# Sheet2.net
KiCad netlist of a schematic drawn in Altium Designer
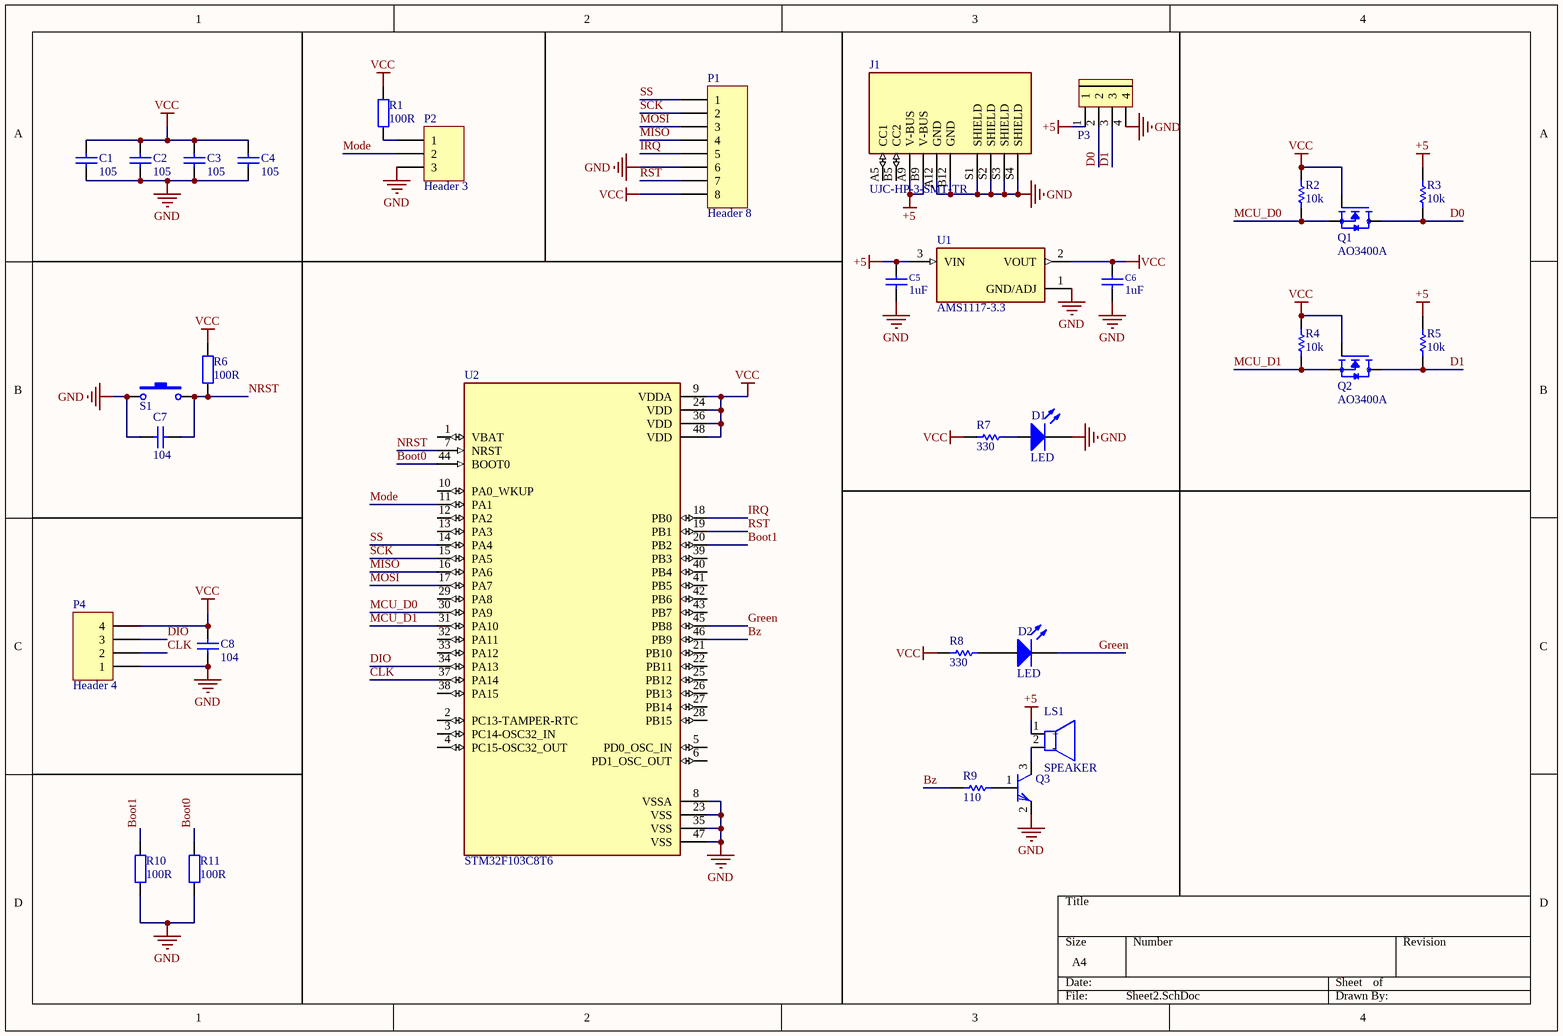
[diagram p0: Sheet2.SchDoc]

(export (version "E")
  (design (tool "Eeschema 10.0.6"))
  (components
    (comp (ref "C1")
      (value "105")
      (footprint "C-NP-0805")
      (description "Non-polarized Capacitor")
      (fields (field (name "Comment") "Cap Non-pol") (field (name "PUBLISHER") "Altium Limited"))
      (libsource (lib "Kiet") (part "Cap Non-pol"))
    )
    (comp (ref "C2")
      (value "105")
      (footprint "C-NP-0805")
      (description "Non-polarized Capacitor")
      (fields (field (name "Comment") "Cap Non-pol") (field (name "PUBLISHER") "Altium Limited"))
      (libsource (lib "Kiet") (part "Cap Non-pol"))
    )
    (comp (ref "C3")
      (value "105")
      (footprint "C-NP-0805")
      (description "Non-polarized Capacitor")
      (fields (field (name "Comment") "Cap Non-pol") (field (name "PUBLISHER") "Altium Limited"))
      (libsource (lib "Kiet") (part "Cap Non-pol"))
    )
    (comp (ref "C4")
      (value "105")
      (footprint "C-NP-0805")
      (description "Non-polarized Capacitor")
      (fields (field (name "Comment") "Cap Non-pol") (field (name "PUBLISHER") "Altium Limited"))
      (libsource (lib "Kiet") (part "Cap Non-pol"))
    )
    (comp (ref "C5")
      (value "1uF")
      (footprint "C2012-0805")
      (description "Capacitor")
      (fields (field (name "PUBLISHER") "Hoang Nguyen"))
      (libsource (lib "Kiet") (part "Capacitor"))
    )
    (comp (ref "C6")
      (value "1uF")
      (footprint "C2012-0805")
      (description "Capacitor")
      (fields (field (name "PUBLISHER") "Hoang Nguyen"))
      (libsource (lib "Kiet") (part "Capacitor"))
    )
    (comp (ref "C7")
      (value "104")
      (footprint "C-NP-0805")
      (description "Non-polarized Capacitor")
      (fields (field (name "Comment") "Cap Non-pol") (field (name "PUBLISHER") "Altium Limited"))
      (libsource (lib "Kiet") (part "Cap Non-pol"))
    )
    (comp (ref "C8")
      (value "104")
      (footprint "C-NP-0805")
      (description "Non-polarized Capacitor")
      (fields (field (name "Comment") "Cap Non-pol") (field (name "PUBLISHER") "Altium Limited"))
      (libsource (lib "Kiet") (part "Cap Non-pol"))
    )
    (comp (ref "D1")
      (value "LED")
      (footprint "LED-0805 RED")
      (description "Typical LED")
      (fields (field (name "PUBLISHER") "Altium Limited"))
      (libsource (lib "Kiet") (part "LED"))
    )
    (comp (ref "D2")
      (value "LED")
      (footprint "LED-0 3mm RED")
      (description "Typical LED")
      (fields (field (name "PUBLISHER") "Altium Limited"))
      (libsource (lib "Kiet") (part "LED"))
    )
    (comp (ref "J1")
      (value "UJC-HP-3-SMT-TR")
      (footprint "CUI_UJC-HP-3-SMT-TR")
      (libsource (lib "UJC-HP-3-SMT-TR") (part "UJC-HP-3-SMT-TR"))
    )
    (comp (ref "LS1")
      (value "SPEAKER")
      (footprint "speaker")
      (fields (field (name "PUBLISHER") "Hoang Nguyen"))
      (libsource (lib "Kiet") (part "SPEAKER"))
    )
    (comp (ref "P1")
      (value "Header 8")
      (footprint "Header 8")
      (description "Header, 8-Pin")
      (fields (field (name "PUBLISHER") "Altium Limited"))
      (libsource (lib "Kiet") (part "Header 8"))
    )
    (comp (ref "P2")
      (value "Header 3")
      (footprint "Header 3")
      (description "Header, 3-Pin")
      (fields (field (name "PUBLISHER") "Altium Limited"))
      (libsource (lib "Kiet") (part "Header 3"))
    )
    (comp (ref "P3")
      (value "BIG Header 4")
      (footprint "BIG_Header 4")
      (libsource (lib "Kiet") (part "BIG_Header 4"))
    )
    (comp (ref "P4")
      (value "Header 4")
      (footprint "Header 4")
      (description "Header, 4-Pin")
      (fields (field (name "PUBLISHER") "Altium Limited"))
      (libsource (lib "Kiet") (part "Header 4"))
    )
    (comp (ref "Q1")
      (value "AO3400A")
      (footprint "SOT95P280X125-3N")
      (description "Trans MOSFET N-CH 30V 5.7A 3-Pin SOT-23")
      (libsource (lib "AO3400A") (part "AO3400A"))
    )
    (comp (ref "Q2")
      (value "AO3400A")
      (footprint "SOT95P280X125-3N")
      (description "Trans MOSFET N-CH 30V 5.7A 3-Pin SOT-23")
      (libsource (lib "AO3400A") (part "AO3400A"))
    )
    (comp (ref "Q3")
      (value "C1815")
      (footprint "SOT23 [C1815]")
      (description "Q2SC1815")
      (fields (field (name "PUBLISHER") "Hoang Nguyen"))
      (libsource (lib "Kiet") (part "C1815"))
    )
    (comp (ref "R1")
      (value "100R")
      (footprint "DIEN TRO 0805")
      (description "RES_0805")
      (fields (field (name "Comment") "RES_SMD_0805") (field (name "PUBLISHER") "Altium Limited"))
      (libsource (lib "Kiet") (part "RES_SMD_0805"))
    )
    (comp (ref "R2")
      (value "10k")
      (footprint "R-0805")
      (description "Resistor")
      (fields (field (name "Comment") "RESISTOR") (field (name "PUBLISHER") "Altium Limited"))
      (libsource (lib "Kiet") (part "RESISTOR"))
    )
    (comp (ref "R3")
      (value "10k")
      (footprint "R-0805")
      (description "Resistor")
      (fields (field (name "Comment") "RESISTOR") (field (name "PUBLISHER") "Altium Limited"))
      (libsource (lib "Kiet") (part "RESISTOR"))
    )
    (comp (ref "R4")
      (value "10k")
      (footprint "R-0805")
      (description "Resistor")
      (fields (field (name "Comment") "RESISTOR") (field (name "PUBLISHER") "Altium Limited"))
      (libsource (lib "Kiet") (part "RESISTOR"))
    )
    (comp (ref "R5")
      (value "10k")
      (footprint "R-0805")
      (description "Resistor")
      (fields (field (name "Comment") "RESISTOR") (field (name "PUBLISHER") "Altium Limited"))
      (libsource (lib "Kiet") (part "RESISTOR"))
    )
    (comp (ref "R6")
      (value "100R")
      (footprint "DIEN TRO 0805")
      (description "RES_0805")
      (fields (field (name "Comment") "RES_SMD_0805") (field (name "PUBLISHER") "Altium Limited"))
      (libsource (lib "Kiet") (part "RES_SMD_0805"))
    )
    (comp (ref "R7")
      (value "330")
      (footprint "R-0805")
      (description "Resistor")
      (fields (field (name "Comment") "RESISTOR") (field (name "PUBLISHER") "Altium Limited"))
      (libsource (lib "Kiet") (part "RESISTOR"))
    )
    (comp (ref "R8")
      (value "330")
      (footprint "R-0805")
      (description "Resistor")
      (fields (field (name "Comment") "RESISTOR") (field (name "PUBLISHER") "Altium Limited"))
      (libsource (lib "Kiet") (part "RESISTOR"))
    )
    (comp (ref "R9")
      (value "110")
      (footprint "R-0805")
      (description "Resistor")
      (fields (field (name "Comment") "RESISTOR") (field (name "PUBLISHER") "Altium Limited"))
      (libsource (lib "Kiet") (part "RESISTOR"))
    )
    (comp (ref "R10")
      (value "100R")
      (footprint "DIEN TRO 0805")
      (description "RES_0805")
      (fields (field (name "Comment") "RES_SMD_0805") (field (name "PUBLISHER") "Altium Limited"))
      (libsource (lib "") (part "RES_SMD_0805_1"))
    )
    (comp (ref "R11")
      (value "100R")
      (footprint "DIEN TRO 0805")
      (description "RES_0805")
      (fields (field (name "Comment") "RES_SMD_0805") (field (name "PUBLISHER") "Altium Limited"))
      (libsource (lib "Kiet") (part "RES_SMD_0805"))
    )
    (comp (ref "S1")
      (value "SW-SMD")
      (footprint "SW-SMD")
      (description "Switch")
      (fields (field (name "PUBLISHER") "Altium Limited"))
      (libsource (lib "Kiet") (part "SW-SMD"))
    )
    (comp (ref "U1")
      (value "AMS1117-3.3")
      (footprint "SOT229P700X180-4N")
      (description "Sot223/Pkg 1-Amp 3.3-Volt Low Drop Out Voltage Regulatator")
      (fields (field (name "MF") "Advanced Monolithic Systems"))
      (libsource (lib "AMS1117-3.3") (part "AMS1117-3.3"))
    )
    (comp (ref "U2")
      (value "STM32F103C8T6")
      (footprint "QFP50P900X900X160-48N")
      (description "ARM® Cortex®-M3 STM32F1 Microcontroller IC 32-Bit 72MHz 64KB (64K x 8) FLASH 48-LQFP (7x7)")
      (fields (field (name "MF") "STMicroelectronics"))
      (libsource (lib "STM32F103C8T6") (part "STM32F103C8T6"))
    )
  )
  (nets
    (net (code "1") (name "+5") (class "Default")
      (node (ref "C5") (pin "2") (pinfunction "2_2") (pintype "passive"))
      (node (ref "J1") (pin "A9") (pinfunction "V-BUS_A9") (pintype "power_in"))
      (node (ref "J1") (pin "B9") (pinfunction "V-BUS_B9") (pintype "power_in"))
      (node (ref "LS1") (pin "1") (pinfunction "+_1") (pintype "passive"))
      (node (ref "P3") (pin "1") (pinfunction "1_1") (pintype "passive"))
      (node (ref "R3") (pin "2") (pinfunction "2_2") (pintype "passive"))
      (node (ref "R5") (pin "2") (pinfunction "2_2") (pintype "passive"))
      (node (ref "U1") (pin "3") (pinfunction "VIN_3") (pintype "input"))
    )
    (net (code "2") (name "/Boot0") (class "Default")
      (node (ref "R11") (pin "2") (pinfunction "2_2") (pintype "passive"))
      (node (ref "U2") (pin "44") (pinfunction "BOOT0_44") (pintype "input"))
    )
    (net (code "3") (name "/Boot1") (class "Default")
      (node (ref "R10") (pin "1") (pinfunction "1_1") (pintype "passive"))
      (node (ref "U2") (pin "20") (pinfunction "PB2_20") (pintype "bidirectional"))
    )
    (net (code "4") (name "/Bz") (class "Default")
      (node (ref "R9") (pin "1") (pinfunction "1_1") (pintype "passive"))
      (node (ref "U2") (pin "46") (pinfunction "PB9_46") (pintype "bidirectional"))
    )
    (net (code "5") (name "/CLK") (class "Default")
      (node (ref "P4") (pin "2") (pinfunction "2_2") (pintype "passive"))
      (node (ref "U2") (pin "37") (pinfunction "PA14_37") (pintype "bidirectional"))
    )
    (net (code "6") (name "/D0") (class "Default")
      (node (ref "P3") (pin "2") (pinfunction "2_2") (pintype "passive"))
      (node (ref "Q1") (pin "3") (pinfunction "D_3") (pintype "passive"))
      (node (ref "R3") (pin "1") (pinfunction "1_1") (pintype "passive"))
    )
    (net (code "7") (name "/D1") (class "Default")
      (node (ref "P3") (pin "3") (pinfunction "3_3") (pintype "passive"))
      (node (ref "Q2") (pin "3") (pinfunction "D_3") (pintype "passive"))
      (node (ref "R5") (pin "1") (pinfunction "1_1") (pintype "passive"))
    )
    (net (code "8") (name "/DIO") (class "Default")
      (node (ref "P4") (pin "3") (pinfunction "3_3") (pintype "passive"))
      (node (ref "U2") (pin "34") (pinfunction "PA13_34") (pintype "bidirectional"))
    )
    (net (code "9") (name "/Green") (class "Default")
      (node (ref "D2") (pin "2") (pinfunction "K_2") (pintype "passive"))
      (node (ref "U2") (pin "45") (pinfunction "PB8_45") (pintype "bidirectional"))
    )
    (net (code "10") (name "/IRQ") (class "Default")
      (node (ref "P1") (pin "5") (pinfunction "5_5") (pintype "passive"))
      (node (ref "U2") (pin "18") (pinfunction "PB0_18") (pintype "bidirectional"))
    )
    (net (code "11") (name "/MCU_D0") (class "Default")
      (node (ref "Q1") (pin "2") (pinfunction "S_2") (pintype "passive"))
      (node (ref "R2") (pin "1") (pinfunction "1_1") (pintype "passive"))
      (node (ref "U2") (pin "30") (pinfunction "PA9_30") (pintype "bidirectional"))
    )
    (net (code "12") (name "/MCU_D1") (class "Default")
      (node (ref "Q2") (pin "2") (pinfunction "S_2") (pintype "passive"))
      (node (ref "R4") (pin "1") (pinfunction "1_1") (pintype "passive"))
      (node (ref "U2") (pin "31") (pinfunction "PA10_31") (pintype "bidirectional"))
    )
    (net (code "13") (name "/MISO") (class "Default")
      (node (ref "P1") (pin "4") (pinfunction "4_4") (pintype "passive"))
      (node (ref "U2") (pin "16") (pinfunction "PA6_16") (pintype "bidirectional"))
    )
    (net (code "14") (name "/MOSI") (class "Default")
      (node (ref "P1") (pin "3") (pinfunction "3_3") (pintype "passive"))
      (node (ref "U2") (pin "17") (pinfunction "PA7_17") (pintype "bidirectional"))
    )
    (net (code "15") (name "/Mode") (class "Default")
      (node (ref "P2") (pin "2") (pinfunction "2_2") (pintype "passive"))
      (node (ref "U2") (pin "11") (pinfunction "PA1_11") (pintype "bidirectional"))
    )
    (net (code "16") (name "/NRST") (class "Default")
      (node (ref "C7") (pin "1") (pinfunction "1_1") (pintype "passive"))
      (node (ref "R6") (pin "1") (pinfunction "1_1") (pintype "passive"))
      (node (ref "S1") (pin "2") (pinfunction "2_2") (pintype "passive"))
      (node (ref "U2") (pin "7") (pinfunction "NRST_7") (pintype "input"))
    )
    (net (code "17") (name "/RST") (class "Default")
      (node (ref "P1") (pin "7") (pinfunction "7_7") (pintype "passive"))
      (node (ref "U2") (pin "19") (pinfunction "PB1_19") (pintype "bidirectional"))
    )
    (net (code "18") (name "/SCK") (class "Default")
      (node (ref "P1") (pin "2") (pinfunction "2_2") (pintype "passive"))
      (node (ref "U2") (pin "15") (pinfunction "PA5_15") (pintype "bidirectional"))
    )
    (net (code "19") (name "/SS") (class "Default")
      (node (ref "P1") (pin "1") (pinfunction "1_1") (pintype "passive"))
      (node (ref "U2") (pin "14") (pinfunction "PA4_14") (pintype "bidirectional"))
    )
    (net (code "20") (name "GND") (class "Default")
      (node (ref "C1") (pin "1") (pinfunction "1_1") (pintype "passive"))
      (node (ref "C2") (pin "1") (pinfunction "1_1") (pintype "passive"))
      (node (ref "C3") (pin "1") (pinfunction "1_1") (pintype "passive"))
      (node (ref "C4") (pin "1") (pinfunction "1_1") (pintype "passive"))
      (node (ref "C5") (pin "1") (pinfunction "1_1") (pintype "passive"))
      (node (ref "C6") (pin "2") (pinfunction "2_2") (pintype "passive"))
      (node (ref "C7") (pin "2") (pinfunction "2_2") (pintype "passive"))
      (node (ref "C8") (pin "2") (pinfunction "2_2") (pintype "passive"))
      (node (ref "D1") (pin "2") (pinfunction "K_2") (pintype "passive"))
      (node (ref "J1") (pin "A12") (pinfunction "GND_A12") (pintype "power_in"))
      (node (ref "J1") (pin "B12") (pinfunction "GND_B12") (pintype "power_in"))
      (node (ref "J1") (pin "S1") (pinfunction "SHIELD_S1") (pintype "passive"))
      (node (ref "J1") (pin "S2") (pinfunction "SHIELD_S2") (pintype "passive"))
      (node (ref "J1") (pin "S3") (pinfunction "SHIELD_S3") (pintype "passive"))
      (node (ref "J1") (pin "S4") (pinfunction "SHIELD_S4") (pintype "passive"))
      (node (ref "P1") (pin "6") (pinfunction "6_6") (pintype "passive"))
      (node (ref "P2") (pin "3") (pinfunction "3_3") (pintype "passive"))
      (node (ref "P3") (pin "4") (pinfunction "4_4") (pintype "passive"))
      (node (ref "P4") (pin "1") (pinfunction "1_1") (pintype "passive"))
      (node (ref "Q3") (pin "2") (pinfunction "E_2") (pintype "passive"))
      (node (ref "R10") (pin "2") (pinfunction "2_2") (pintype "passive"))
      (node (ref "R11") (pin "1") (pinfunction "1_1") (pintype "passive"))
      (node (ref "S1") (pin "1") (pinfunction "1_1") (pintype "passive"))
      (node (ref "U1") (pin "1") (pinfunction "GND/ADJ_1") (pintype "power_in"))
      (node (ref "U2") (pin "23") (pinfunction "VSS_23") (pintype "power_in"))
      (node (ref "U2") (pin "35") (pinfunction "VSS_35") (pintype "power_in"))
      (node (ref "U2") (pin "47") (pinfunction "VSS_47") (pintype "power_in"))
      (node (ref "U2") (pin "8") (pinfunction "VSSA_8") (pintype "power_in"))
    )
    (net (code "21") (name "Net-(D1-A)") (class "Default")
      (node (ref "D1") (pin "1") (pinfunction "A_1") (pintype "passive"))
      (node (ref "R7") (pin "2") (pinfunction "2_2") (pintype "passive"))
    )
    (net (code "22") (name "Net-(D2-A)") (class "Default")
      (node (ref "D2") (pin "1") (pinfunction "A_1") (pintype "passive"))
      (node (ref "R8") (pin "2") (pinfunction "2_2") (pintype "passive"))
    )
    (net (code "23") (name "Net-(LS1--)") (class "Default")
      (node (ref "LS1") (pin "2") (pinfunction "-_2") (pintype "passive"))
      (node (ref "Q3") (pin "3") (pinfunction "C_3") (pintype "passive"))
    )
    (net (code "24") (name "Net-(P2-Pad1)") (class "Default")
      (node (ref "P2") (pin "1") (pinfunction "1_1") (pintype "passive"))
      (node (ref "R1") (pin "1") (pinfunction "1_1") (pintype "passive"))
    )
    (net (code "25") (name "Net-(Q3-B)") (class "Default")
      (node (ref "Q3") (pin "1") (pinfunction "B_1") (pintype "passive"))
      (node (ref "R9") (pin "2") (pinfunction "2_2") (pintype "passive"))
    )
    (net (code "26") (name "VCC") (class "Default")
      (node (ref "C1") (pin "2") (pinfunction "2_2") (pintype "passive"))
      (node (ref "C2") (pin "2") (pinfunction "2_2") (pintype "passive"))
      (node (ref "C3") (pin "2") (pinfunction "2_2") (pintype "passive"))
      (node (ref "C4") (pin "2") (pinfunction "2_2") (pintype "passive"))
      (node (ref "C6") (pin "1") (pinfunction "1_1") (pintype "passive"))
      (node (ref "C8") (pin "1") (pinfunction "1_1") (pintype "passive"))
      (node (ref "P1") (pin "8") (pinfunction "8_8") (pintype "passive"))
      (node (ref "P4") (pin "4") (pinfunction "4_4") (pintype "passive"))
      (node (ref "Q1") (pin "1") (pinfunction "G_1") (pintype "passive"))
      (node (ref "Q2") (pin "1") (pinfunction "G_1") (pintype "passive"))
      (node (ref "R1") (pin "2") (pinfunction "2_2") (pintype "passive"))
      (node (ref "R2") (pin "2") (pinfunction "2_2") (pintype "passive"))
      (node (ref "R4") (pin "2") (pinfunction "2_2") (pintype "passive"))
      (node (ref "R6") (pin "2") (pinfunction "2_2") (pintype "passive"))
      (node (ref "R7") (pin "1") (pinfunction "1_1") (pintype "passive"))
      (node (ref "R8") (pin "1") (pinfunction "1_1") (pintype "passive"))
      (node (ref "U1") (pin "2") (pinfunction "VOUT_2") (pintype "output"))
      (node (ref "U2") (pin "24") (pinfunction "VDD_24") (pintype "power_in"))
      (node (ref "U2") (pin "36") (pinfunction "VDD_36") (pintype "power_in"))
      (node (ref "U2") (pin "48") (pinfunction "VDD_48") (pintype "power_in"))
      (node (ref "U2") (pin "9") (pinfunction "VDDA_9") (pintype "power_in"))
    )
    (net (code "27") (name "unconnected-(J1-CC1-PadA5)") (class "Default")
      (node (ref "J1") (pin "A5") (pinfunction "CC1_A5") (pintype "bidirectional"))
    )
    (net (code "28") (name "unconnected-(J1-CC2-PadB5)") (class "Default")
      (node (ref "J1") (pin "B5") (pinfunction "CC2_B5") (pintype "bidirectional"))
    )
    (net (code "29") (name "unconnected-(U2-PA0_WKUP-Pad10)") (class "Default")
      (node (ref "U2") (pin "10") (pinfunction "PA0_WKUP_10") (pintype "bidirectional"))
    )
    (net (code "30") (name "unconnected-(U2-PA2-Pad12)") (class "Default")
      (node (ref "U2") (pin "12") (pinfunction "PA2_12") (pintype "bidirectional"))
    )
    (net (code "31") (name "unconnected-(U2-PA3-Pad13)") (class "Default")
      (node (ref "U2") (pin "13") (pinfunction "PA3_13") (pintype "bidirectional"))
    )
    (net (code "32") (name "unconnected-(U2-PA8-Pad29)") (class "Default")
      (node (ref "U2") (pin "29") (pinfunction "PA8_29") (pintype "bidirectional"))
    )
    (net (code "33") (name "unconnected-(U2-PA11-Pad32)") (class "Default")
      (node (ref "U2") (pin "32") (pinfunction "PA11_32") (pintype "bidirectional"))
    )
    (net (code "34") (name "unconnected-(U2-PA12-Pad33)") (class "Default")
      (node (ref "U2") (pin "33") (pinfunction "PA12_33") (pintype "bidirectional"))
    )
    (net (code "35") (name "unconnected-(U2-PA15-Pad38)") (class "Default")
      (node (ref "U2") (pin "38") (pinfunction "PA15_38") (pintype "bidirectional"))
    )
    (net (code "36") (name "unconnected-(U2-PB3-Pad39)") (class "Default")
      (node (ref "U2") (pin "39") (pinfunction "PB3_39") (pintype "bidirectional"))
    )
    (net (code "37") (name "unconnected-(U2-PB4-Pad40)") (class "Default")
      (node (ref "U2") (pin "40") (pinfunction "PB4_40") (pintype "bidirectional"))
    )
    (net (code "38") (name "unconnected-(U2-PB5-Pad41)") (class "Default")
      (node (ref "U2") (pin "41") (pinfunction "PB5_41") (pintype "bidirectional"))
    )
    (net (code "39") (name "unconnected-(U2-PB6-Pad42)") (class "Default")
      (node (ref "U2") (pin "42") (pinfunction "PB6_42") (pintype "bidirectional"))
    )
    (net (code "40") (name "unconnected-(U2-PB7-Pad43)") (class "Default")
      (node (ref "U2") (pin "43") (pinfunction "PB7_43") (pintype "bidirectional"))
    )
    (net (code "41") (name "unconnected-(U2-PB10-Pad21)") (class "Default")
      (node (ref "U2") (pin "21") (pinfunction "PB10_21") (pintype "bidirectional"))
    )
    (net (code "42") (name "unconnected-(U2-PB11-Pad22)") (class "Default")
      (node (ref "U2") (pin "22") (pinfunction "PB11_22") (pintype "bidirectional"))
    )
    (net (code "43") (name "unconnected-(U2-PB12-Pad25)") (class "Default")
      (node (ref "U2") (pin "25") (pinfunction "PB12_25") (pintype "bidirectional"))
    )
    (net (code "44") (name "unconnected-(U2-PB13-Pad26)") (class "Default")
      (node (ref "U2") (pin "26") (pinfunction "PB13_26") (pintype "bidirectional"))
    )
    (net (code "45") (name "unconnected-(U2-PB14-Pad27)") (class "Default")
      (node (ref "U2") (pin "27") (pinfunction "PB14_27") (pintype "bidirectional"))
    )
    (net (code "46") (name "unconnected-(U2-PB15-Pad28)") (class "Default")
      (node (ref "U2") (pin "28") (pinfunction "PB15_28") (pintype "bidirectional"))
    )
    (net (code "47") (name "unconnected-(U2-PC13-TAMPER-RTC-Pad2)") (class "Default")
      (node (ref "U2") (pin "2") (pinfunction "PC13-TAMPER-RTC_2") (pintype "bidirectional"))
    )
    (net (code "48") (name "unconnected-(U2-PC14-OSC32_IN-Pad3)") (class "Default")
      (node (ref "U2") (pin "3") (pinfunction "PC14-OSC32_IN_3") (pintype "bidirectional"))
    )
    (net (code "49") (name "unconnected-(U2-PC15-OSC32_OUT-Pad4)") (class "Default")
      (node (ref "U2") (pin "4") (pinfunction "PC15-OSC32_OUT_4") (pintype "bidirectional"))
    )
    (net (code "50") (name "unconnected-(U2-PD0_OSC_IN-Pad5)") (class "Default")
      (node (ref "U2") (pin "5") (pinfunction "PD0_OSC_IN_5") (pintype "bidirectional"))
    )
    (net (code "51") (name "unconnected-(U2-PD1_OSC_OUT-Pad6)") (class "Default")
      (node (ref "U2") (pin "6") (pinfunction "PD1_OSC_OUT_6") (pintype "bidirectional"))
    )
    (net (code "52") (name "unconnected-(U2-VBAT-Pad1)") (class "Default")
      (node (ref "U2") (pin "1") (pinfunction "VBAT_1") (pintype "bidirectional"))
    )
  )
)
